# MCU.net
KiCad netlist of a schematic drawn in Altium Designer
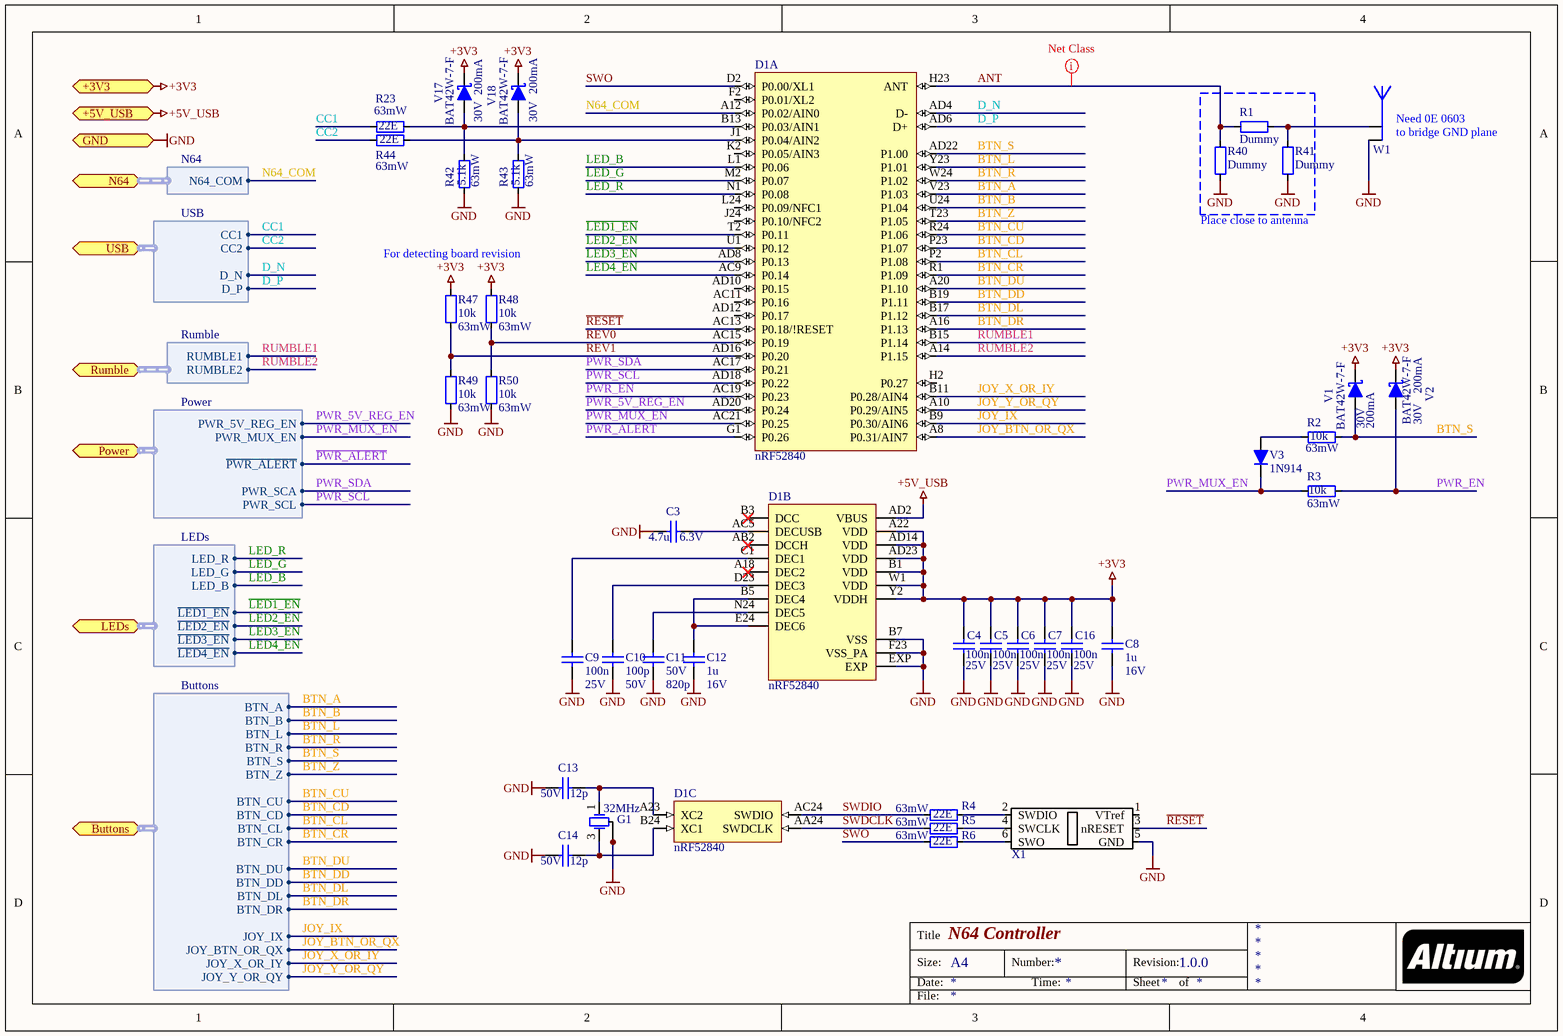
[diagram p0: MCU.SchDoc]

(export (version "E")
  (design (tool "Eeschema 10.0.6"))
  (components
    (comp (ref "C3")
      (value "4.7u")
      (footprint "SMD_CAP_0603")
      (fields (field (name "VALUE2") "6.3V") (field (name "Comment") "C_SMD_CER_4U7_6V3_10%_X5R_0603"))
      (libsource (lib "AM") (part "C_SMD_CER_4U7_6V3_10%_X5R_0603"))
    )
    (comp (ref "C4")
      (value "100n")
      (footprint "SMD_CAP_0402")
      (description "0.1µF ±10% 25V Ceramic Capacitor X7R 0402 (1005 Metric)")
      (fields (field (name "VALUE2") "25V") (field (name "Comment") "C_SMD_CER_100N_25V_10%_X7R_0402"))
      (libsource (lib "AM") (part "C_SMD_CER_100N_25V_10%_X7R_0402"))
    )
    (comp (ref "C5")
      (value "100n")
      (footprint "SMD_CAP_0402")
      (description "0.1µF ±10% 25V Ceramic Capacitor X7R 0402 (1005 Metric)")
      (fields (field (name "VALUE2") "25V") (field (name "Comment") "C_SMD_CER_100N_25V_10%_X7R_0402"))
      (libsource (lib "AM") (part "C_SMD_CER_100N_25V_10%_X7R_0402"))
    )
    (comp (ref "C6")
      (value "100n")
      (footprint "SMD_CAP_0402")
      (description "0.1µF ±10% 25V Ceramic Capacitor X7R 0402 (1005 Metric)")
      (fields (field (name "VALUE2") "25V") (field (name "Comment") "C_SMD_CER_100N_25V_10%_X7R_0402"))
      (libsource (lib "AM") (part "C_SMD_CER_100N_25V_10%_X7R_0402"))
    )
    (comp (ref "C7")
      (value "100n")
      (footprint "SMD_CAP_0402")
      (description "0.1µF ±10% 25V Ceramic Capacitor X7R 0402 (1005 Metric)")
      (fields (field (name "VALUE2") "25V") (field (name "Comment") "C_SMD_CER_100N_25V_10%_X7R_0402"))
      (libsource (lib "AM") (part "C_SMD_CER_100N_25V_10%_X7R_0402"))
    )
    (comp (ref "C8")
      (value "1u")
      (footprint "SMD_CAP_0603")
      (description "1µF ±10% 16V Ceramic Capacitor X7R 0603 (1608 Metric)")
      (fields (field (name "VALUE2") "16V") (field (name "Comment") "C_SMD_CER_1U_16V_10%_X7R_0603"))
      (libsource (lib "AM") (part "C_SMD_CER_1U_16V_10%_X7R_0603"))
    )
    (comp (ref "C9")
      (value "100n")
      (footprint "SMD_CAP_0402")
      (description "0.1µF ±10% 25V Ceramic Capacitor X7R 0402 (1005 Metric)")
      (fields (field (name "VALUE2") "25V") (field (name "Comment") "C_SMD_CER_100N_25V_10%_X7R_0402"))
      (libsource (lib "AM") (part "C_SMD_CER_100N_25V_10%_X7R_0402"))
    )
    (comp (ref "C10")
      (value "100p")
      (footprint "SMD_CAP_0402")
      (fields (field (name "VALUE2") "50V") (field (name "Comment") "C_SMD_CER_100P_50V_5%_NP0_0402"))
      (libsource (lib "AM") (part "C_SMD_CER_100P_50V_5%_NP0_0402"))
    )
    (comp (ref "C11")
      (value "820p")
      (footprint "SMD_CAP_0402")
      (description "820pF ±5% 50V Ceramic Capacitor C0G, NP0 0402 (1005 Metric)")
      (fields (field (name "VALUE2") "50V") (field (name "Comment") "C_SMD_CER_820P_50V_5%_NP0_0402"))
      (libsource (lib "AM") (part "C_SMD_CER_820P_50V_5%_NP0_0402"))
    )
    (comp (ref "C12")
      (value "1u")
      (footprint "SMD_CAP_0603")
      (description "1µF ±10% 16V Ceramic Capacitor X7R 0603 (1608 Metric)")
      (fields (field (name "VALUE2") "16V") (field (name "Comment") "C_SMD_CER_1U_16V_10%_X7R_0603"))
      (libsource (lib "AM") (part "C_SMD_CER_1U_16V_10%_X7R_0603"))
    )
    (comp (ref "C13")
      (value "12p")
      (footprint "SMD_CAP_0402")
      (description "12pF ±2% 50V Ceramic Capacitor C0G, NP0 0402 (1005 Metric)")
      (fields (field (name "VALUE2") "50V") (field (name "Comment") "C_SMD_CER_12P_50V_2%_NP0_0402"))
      (libsource (lib "AM") (part "C_SMD_CER_12P_50V_2%_NP0_0402"))
    )
    (comp (ref "C14")
      (value "12p")
      (footprint "SMD_CAP_0402")
      (description "12pF ±2% 50V Ceramic Capacitor C0G, NP0 0402 (1005 Metric)")
      (fields (field (name "VALUE2") "50V") (field (name "Comment") "C_SMD_CER_12P_50V_2%_NP0_0402"))
      (libsource (lib "AM") (part "C_SMD_CER_12P_50V_2%_NP0_0402"))
    )
    (comp (ref "C16")
      (value "100n")
      (footprint "SMD_CAP_0402")
      (description "0.1µF ±10% 25V Ceramic Capacitor X7R 0402 (1005 Metric)")
      (fields (field (name "VALUE2") "25V") (field (name "Comment") "C_SMD_CER_100N_25V_10%_X7R_0402"))
      (libsource (lib "AM") (part "C_SMD_CER_100N_25V_10%_X7R_0402"))
    )
    (comp (ref "D1")
      (value "D_NRF52840_aQFN-73")
      (footprint "SMD_aQFN_73_nRF52840")
      (description "IC RF TxRx + MCU 802.15.4, Bluetooth Bluetooth v5.0 2.4GHz 73-VFQFN Dual Rows, Exposed Pad")
      (fields (field (name "TYPE") "nRF52840"))
      (libsource (lib "") (part "D_NRF52840_aQFN-73_1"))
    )
    (comp (ref "G1")
      (value "32MHz")
      (footprint "SMD_QUARZ_3.2X2.5")
      (description "32MHz ±10ppm Crystal 8pF 40 Ohms 4-SMD, No Lead")
      (fields (field (name "Comment") "G_SMD_OSC_XTAL_32MHZ_10PPM_8PF_40OHM"))
      (libsource (lib "AM") (part "G_SMD_OSC_XTAL_32MHZ_10PPM_8PF_40OHM"))
    )
    (comp (ref "R1")
      (value "Dummy")
      (footprint "SMD_RES_0402")
      (description "Dummy 0402")
      (libsource (lib "AM") (part "R_SMD_DUMMY_0402"))
    )
    (comp (ref "R2")
      (value "10k")
      (footprint "SMD_RES_0402")
      (description "SMD Resistor")
      (fields
        (field (name "VALUE2") "63mW")
        (field (name "Comment") "R_SMD_THINFILM_10K_0W063_0%5_25PPM_0402")
      )
      (libsource (lib "AM") (part "R_SMD_THINFILM_10K_0W063_0%5_25PPM_0402"))
    )
    (comp (ref "R3")
      (value "10k")
      (footprint "SMD_RES_0402")
      (description "SMD Resistor")
      (fields
        (field (name "VALUE2") "63mW")
        (field (name "Comment") "R_SMD_THINFILM_10K_0W063_0%5_25PPM_0402")
      )
      (libsource (lib "AM") (part "R_SMD_THINFILM_10K_0W063_0%5_25PPM_0402"))
    )
    (comp (ref "R4")
      (value "22E")
      (footprint "SMD_RES_0402")
      (description "22 Ohms ±1% 0.063W, 1/16W Chip Resistor 0402 (1005 Metric) Moisture Resistant Thick Film")
      (fields
        (field (name "VALUE2") "63mW")
        (field (name "Comment") "R_SMD_THICKFILM_22E_0W063_1%_100PPM_0402")
      )
      (libsource (lib "AM") (part "R_SMD_THICKFILM_22E_0W063_1%_100PPM_0402"))
    )
    (comp (ref "R5")
      (value "22E")
      (footprint "SMD_RES_0402")
      (description "22 Ohms ±1% 0.063W, 1/16W Chip Resistor 0402 (1005 Metric) Moisture Resistant Thick Film")
      (fields
        (field (name "VALUE2") "63mW")
        (field (name "Comment") "R_SMD_THICKFILM_22E_0W063_1%_100PPM_0402")
      )
      (libsource (lib "AM") (part "R_SMD_THICKFILM_22E_0W063_1%_100PPM_0402"))
    )
    (comp (ref "R6")
      (value "22E")
      (footprint "SMD_RES_0402")
      (description "22 Ohms ±1% 0.063W, 1/16W Chip Resistor 0402 (1005 Metric) Moisture Resistant Thick Film")
      (fields
        (field (name "VALUE2") "63mW")
        (field (name "Comment") "R_SMD_THICKFILM_22E_0W063_1%_100PPM_0402")
      )
      (libsource (lib "AM") (part "R_SMD_THICKFILM_22E_0W063_1%_100PPM_0402"))
    )
    (comp (ref "R23")
      (value "22E")
      (footprint "SMD_RES_0402")
      (description "22 Ohms ±1% 0.063W, 1/16W Chip Resistor 0402 (1005 Metric) Moisture Resistant Thick Film")
      (fields
        (field (name "VALUE2") "63mW")
        (field (name "Comment") "R_SMD_THICKFILM_22E_0W063_1%_100PPM_0402")
      )
      (libsource (lib "AM") (part "R_SMD_THICKFILM_22E_0W063_1%_100PPM_0402"))
    )
    (comp (ref "R40")
      (value "Dummy")
      (footprint "SMD_RES_0402")
      (description "Dummy 0402")
      (libsource (lib "AM") (part "R_SMD_DUMMY_0402"))
    )
    (comp (ref "R41")
      (value "Dummy")
      (footprint "SMD_RES_0402")
      (description "Dummy 0402")
      (libsource (lib "AM") (part "R_SMD_DUMMY_0402"))
    )
    (comp (ref "R42")
      (value "5.1k")
      (footprint "SMD_CAP_0402")
      (description "5.1 kOhms ±0.5% 0.063W, 1/16W Chip Resistor 0402 (1005 Metric) Automotive AEC-Q200 Thin Film")
      (fields
        (field (name "VALUE2") "63mW")
        (field (name "Comment") "R_SMD_THINFILM_5K1_0W063_0%5_25PPM_0402")
      )
      (libsource (lib "AM") (part "R_SMD_THINFILM_5K1_0W063_0%5_25PPM_0402"))
    )
    (comp (ref "R43")
      (value "5.1k")
      (footprint "SMD_CAP_0402")
      (description "5.1 kOhms ±0.5% 0.063W, 1/16W Chip Resistor 0402 (1005 Metric) Automotive AEC-Q200 Thin Film")
      (fields
        (field (name "VALUE2") "63mW")
        (field (name "Comment") "R_SMD_THINFILM_5K1_0W063_0%5_25PPM_0402")
      )
      (libsource (lib "AM") (part "R_SMD_THINFILM_5K1_0W063_0%5_25PPM_0402"))
    )
    (comp (ref "R44")
      (value "22E")
      (footprint "SMD_RES_0402")
      (description "22 Ohms ±1% 0.063W, 1/16W Chip Resistor 0402 (1005 Metric) Moisture Resistant Thick Film")
      (fields
        (field (name "VALUE2") "63mW")
        (field (name "Comment") "R_SMD_THICKFILM_22E_0W063_1%_100PPM_0402")
      )
      (libsource (lib "AM") (part "R_SMD_THICKFILM_22E_0W063_1%_100PPM_0402"))
    )
    (comp (ref "R47")
      (value "10k")
      (footprint "SMD_RES_0402")
      (description "SMD Resistor")
      (fields
        (field (name "VALUE2") "63mW")
        (field (name "Comment") "R_SMD_THINFILM_10K_0W063_0%5_25PPM_0402")
      )
      (libsource (lib "AM") (part "R_SMD_THINFILM_10K_0W063_0%5_25PPM_0402"))
    )
    (comp (ref "R48")
      (value "10k")
      (footprint "SMD_RES_0402")
      (description "SMD Resistor")
      (fields
        (field (name "VALUE2") "63mW")
        (field (name "Comment") "R_SMD_THINFILM_10K_0W063_0%5_25PPM_0402")
      )
      (libsource (lib "AM") (part "R_SMD_THINFILM_10K_0W063_0%5_25PPM_0402"))
    )
    (comp (ref "R49")
      (value "10k")
      (footprint "SMD_RES_0402")
      (description "SMD Resistor")
      (fields
        (field (name "VALUE2") "63mW")
        (field (name "Comment") "R_SMD_THINFILM_10K_0W063_0%5_25PPM_0402")
      )
      (libsource (lib "AM") (part "R_SMD_THINFILM_10K_0W063_0%5_25PPM_0402"))
    )
    (comp (ref "R50")
      (value "10k")
      (footprint "SMD_RES_0402")
      (description "SMD Resistor")
      (fields
        (field (name "VALUE2") "63mW")
        (field (name "Comment") "R_SMD_THINFILM_10K_0W063_0%5_25PPM_0402")
      )
      (libsource (lib "AM") (part "R_SMD_THINFILM_10K_0W063_0%5_25PPM_0402"))
    )
    (comp (ref "V1")
      (value "30V")
      (footprint "SMD_SOD_123")
      (description "Diode Schottky 30V 200mA (DC) Surface Mount SOD-123")
      (fields
        (field (name "TYPE") "BAT42W-7-F")
        (field (name "VALUE2") "200mA")
        (field (name "Comment") "V_SMD_SCHOTTKY_BAT42W-7-F_30V_0A2_SOD-123")
      )
      (libsource (lib "AM") (part "V_SMD_SCHOTTKY_BAT42W-7-F_30V_0A2_SOD-123"))
    )
    (comp (ref "V2")
      (value "30V")
      (footprint "SMD_SOD_123")
      (description "Diode Schottky 30V 200mA (DC) Surface Mount SOD-123")
      (fields
        (field (name "TYPE") "BAT42W-7-F")
        (field (name "VALUE2") "200mA")
        (field (name "Comment") "V_SMD_SCHOTTKY_BAT42W-7-F_30V_0A2_SOD-123")
      )
      (libsource (lib "AM") (part "V_SMD_SCHOTTKY_BAT42W-7-F_30V_0A2_SOD-123"))
    )
    (comp (ref "V3")
      (value "V_SMD_DIODE_1N914_75V_0A15_SOD-323")
      (footprint "SMD_SOD_323")
      (description "SMD Diode, 75V, 0.15A")
      (fields (field (name "TYPE") "1N914"))
      (libsource (lib "AM") (part "V_SMD_DIODE_1N914_75V_0A15_SOD-323"))
    )
    (comp (ref "V17")
      (value "30V")
      (footprint "SMD_SOD_123")
      (description "Diode Schottky 30V 200mA (DC) Surface Mount SOD-123")
      (fields
        (field (name "TYPE") "BAT42W-7-F")
        (field (name "VALUE2") "200mA")
        (field (name "Comment") "V_SMD_SCHOTTKY_BAT42W-7-F_30V_0A2_SOD-123")
      )
      (libsource (lib "AM") (part "V_SMD_SCHOTTKY_BAT42W-7-F_30V_0A2_SOD-123"))
    )
    (comp (ref "V18")
      (value "30V")
      (footprint "SMD_SOD_123")
      (description "Diode Schottky 30V 200mA (DC) Surface Mount SOD-123")
      (fields
        (field (name "TYPE") "BAT42W-7-F")
        (field (name "VALUE2") "200mA")
        (field (name "Comment") "V_SMD_SCHOTTKY_BAT42W-7-F_30V_0A2_SOD-123")
      )
      (libsource (lib "AM") (part "V_SMD_SCHOTTKY_BAT42W-7-F_30V_0A2_SOD-123"))
    )
    (comp (ref "W1")
      (value "W_BLUETOOTH_IFA_1MM")
      (footprint "BLUETOOTH_IFA_1MM")
      (description "Single Layer Printed IFA, 1 mm Substrate")
      (libsource (lib "AM") (part "W_BLUETOOTH_IFA_1MM"))
    )
    (comp (ref "X1")
      (value "X_J-LINK_6-PIN_NEEDLE_HEADER")
      (footprint "SMD_J-LINK_6-PIN_NEEDLE")
      (description "J-Link 6-pin Needle Adapter (8.06.16)")
      (libsource (lib "AM") (part "X_J-LINK_6-PIN_NEEDLE_HEADER"))
    )
  )
  (nets
    (net (code "7") (name "+3V3") (class "Default")
      (node (ref "C16") (pin "2") (pinfunction "2_2") (pintype "passive"))
      (node (ref "C4") (pin "2") (pinfunction "2_2") (pintype "passive"))
      (node (ref "C5") (pin "2") (pinfunction "2_2") (pintype "passive"))
      (node (ref "C6") (pin "2") (pinfunction "2_2") (pintype "passive"))
      (node (ref "C7") (pin "2") (pinfunction "2_2") (pintype "passive"))
      (node (ref "C8") (pin "2") (pinfunction "2_2") (pintype "passive"))
      (node (ref "D1") (pin "A22") (pinfunction "VDD_A22") (pintype "power_in"))
      (node (ref "D1") (pin "AD14") (pinfunction "VDD_AD14") (pintype "power_in"))
      (node (ref "D1") (pin "AD23") (pinfunction "VDD_AD23") (pintype "power_in"))
      (node (ref "D1") (pin "B1") (pinfunction "VDD_B1") (pintype "power_in"))
      (node (ref "D1") (pin "W1") (pinfunction "VDD_W1") (pintype "power_in"))
      (node (ref "D1") (pin "Y2") (pinfunction "VDDH_Y2") (pintype "power_in"))
      (node (ref "R47") (pin "1") (pinfunction "1_1") (pintype "passive"))
      (node (ref "R48") (pin "1") (pinfunction "1_1") (pintype "passive"))
      (node (ref "V1") (pin "2") (pinfunction "2_2") (pintype "passive"))
      (node (ref "V17") (pin "2") (pinfunction "2_2") (pintype "passive"))
      (node (ref "V18") (pin "2") (pinfunction "2_2") (pintype "passive"))
      (node (ref "V2") (pin "2") (pinfunction "2_2") (pintype "passive"))
    )
    (net (code "8") (name "+5V_USB") (class "Default")
      (node (ref "D1") (pin "AD2") (pinfunction "VBUS_AD2") (pintype "power_in"))
    )
    (net (code "9") (name "/ANT") (class "Default")
      (node (ref "D1") (pin "H23") (pinfunction "ANT_H23") (pintype "bidirectional"))
      (node (ref "R1") (pin "1") (pinfunction "1_1") (pintype "passive"))
      (node (ref "R40") (pin "2") (pinfunction "2_2") (pintype "passive"))
    )
    (net (code "10") (name "/BTN_A") (class "Default")
      (node (ref "D1") (pin "V23") (pinfunction "P1.03_V23") (pintype "bidirectional"))
    )
    (net (code "11") (name "/BTN_B") (class "Default")
      (node (ref "D1") (pin "U24") (pinfunction "P1.04_U24") (pintype "bidirectional"))
    )
    (net (code "12") (name "/BTN_CD") (class "Default")
      (node (ref "D1") (pin "P23") (pinfunction "P1.07_P23") (pintype "bidirectional"))
    )
    (net (code "13") (name "/BTN_CL") (class "Default")
      (node (ref "D1") (pin "P2") (pinfunction "P1.08_P2") (pintype "bidirectional"))
    )
    (net (code "14") (name "/BTN_CR") (class "Default")
      (node (ref "D1") (pin "R1") (pinfunction "P1.09_R1") (pintype "bidirectional"))
    )
    (net (code "15") (name "/BTN_CU") (class "Default")
      (node (ref "D1") (pin "R24") (pinfunction "P1.06_R24") (pintype "bidirectional"))
    )
    (net (code "16") (name "/BTN_DD") (class "Default")
      (node (ref "D1") (pin "B19") (pinfunction "P1.11_B19") (pintype "bidirectional"))
    )
    (net (code "17") (name "/BTN_DL") (class "Default")
      (node (ref "D1") (pin "B17") (pinfunction "P1.12_B17") (pintype "bidirectional"))
    )
    (net (code "18") (name "/BTN_DR") (class "Default")
      (node (ref "D1") (pin "A16") (pinfunction "P1.13_A16") (pintype "bidirectional"))
    )
    (net (code "19") (name "/BTN_DU") (class "Default")
      (node (ref "D1") (pin "A20") (pinfunction "P1.10_A20") (pintype "bidirectional"))
    )
    (net (code "20") (name "/BTN_L") (class "Default")
      (node (ref "D1") (pin "Y23") (pinfunction "P1.01_Y23") (pintype "bidirectional"))
    )
    (net (code "21") (name "/BTN_R") (class "Default")
      (node (ref "D1") (pin "W24") (pinfunction "P1.02_W24") (pintype "bidirectional"))
    )
    (net (code "22") (name "/BTN_S") (class "Default")
      (node (ref "D1") (pin "AD22") (pinfunction "P1.00_AD22") (pintype "bidirectional"))
      (node (ref "R2") (pin "2") (pinfunction "2_2") (pintype "passive"))
      (node (ref "V1") (pin "1") (pinfunction "1_1") (pintype "passive"))
    )
    (net (code "23") (name "/BTN_Z") (class "Default")
      (node (ref "D1") (pin "T23") (pinfunction "P1.05_T23") (pintype "bidirectional"))
    )
    (net (code "24") (name "/CC1") (class "Default")
      (node (ref "R23") (pin "1") (pinfunction "1_1") (pintype "passive"))
    )
    (net (code "25") (name "/CC2") (class "Default")
      (node (ref "R44") (pin "1") (pinfunction "1_1") (pintype "passive"))
    )
    (net (code "26") (name "/D_N") (class "Default")
      (node (ref "D1") (pin "AD4") (pinfunction "D-_AD4") (pintype "bidirectional"))
    )
    (net (code "27") (name "/D_P") (class "Default")
      (node (ref "D1") (pin "AD6") (pinfunction "D+_AD6") (pintype "bidirectional"))
    )
    (net (code "28") (name "/JOY_BTN_OR_QX") (class "Default")
      (node (ref "D1") (pin "A8") (pinfunction "P0.31/AIN7_A8") (pintype "bidirectional"))
    )
    (net (code "29") (name "/JOY_IX") (class "Default")
      (node (ref "D1") (pin "B9") (pinfunction "P0.30/AIN6_B9") (pintype "bidirectional"))
    )
    (net (code "30") (name "/JOY_X_OR_IY") (class "Default")
      (node (ref "D1") (pin "B11") (pinfunction "P0.28/AIN4_B11") (pintype "bidirectional"))
    )
    (net (code "31") (name "/JOY_Y_OR_QY") (class "Default")
      (node (ref "D1") (pin "A10") (pinfunction "P0.29/AIN5_A10") (pintype "bidirectional"))
    )
    (net (code "32") (name "/LED_B") (class "Default")
      (node (ref "D1") (pin "L1") (pinfunction "P0.06_L1") (pintype "bidirectional"))
    )
    (net (code "33") (name "/LED_G") (class "Default")
      (node (ref "D1") (pin "M2") (pinfunction "P0.07_M2") (pintype "bidirectional"))
    )
    (net (code "34") (name "/LED_R") (class "Default")
      (node (ref "D1") (pin "N1") (pinfunction "P0.08_N1") (pintype "bidirectional"))
    )
    (net (code "35") (name "/N64_COM") (class "Default")
      (node (ref "D1") (pin "A12") (pinfunction "P0.02/AIN0_A12") (pintype "bidirectional"))
    )
    (net (code "36") (name "/PWR_5V_REG_EN") (class "Default")
      (node (ref "D1") (pin "AD20") (pinfunction "P0.24_AD20") (pintype "bidirectional"))
    )
    (net (code "37") (name "/PWR_EN") (class "Default")
      (node (ref "D1") (pin "AC19") (pinfunction "P0.23_AC19") (pintype "bidirectional"))
      (node (ref "R3") (pin "2") (pinfunction "2_2") (pintype "passive"))
      (node (ref "V2") (pin "1") (pinfunction "1_1") (pintype "passive"))
    )
    (net (code "38") (name "/PWR_MUX_EN") (class "Default")
      (node (ref "D1") (pin "AC21") (pinfunction "P0.25_AC21") (pintype "bidirectional"))
      (node (ref "R3") (pin "1") (pinfunction "1_1") (pintype "passive"))
      (node (ref "V3") (pin "2") (pinfunction "2_2") (pintype "passive"))
    )
    (net (code "39") (name "/PWR_SCL") (class "Default")
      (node (ref "D1") (pin "AD18") (pinfunction "P0.22_AD18") (pintype "bidirectional"))
    )
    (net (code "40") (name "/PWR_SDA") (class "Default")
      (node (ref "D1") (pin "AC17") (pinfunction "P0.21_AC17") (pintype "bidirectional"))
    )
    (net (code "41") (name "/REV0") (class "Default")
      (node (ref "D1") (pin "AC15") (pinfunction "P0.19_AC15") (pintype "bidirectional"))
      (node (ref "R48") (pin "2") (pinfunction "2_2") (pintype "passive"))
      (node (ref "R50") (pin "1") (pinfunction "1_1") (pintype "passive"))
    )
    (net (code "42") (name "/REV1") (class "Default")
      (node (ref "D1") (pin "AD16") (pinfunction "P0.20_AD16") (pintype "bidirectional"))
      (node (ref "R47") (pin "2") (pinfunction "2_2") (pintype "passive"))
      (node (ref "R49") (pin "1") (pinfunction "1_1") (pintype "passive"))
    )
    (net (code "43") (name "/RUMBLE1") (class "Default")
      (node (ref "D1") (pin "B15") (pinfunction "P1.14_B15") (pintype "bidirectional"))
    )
    (net (code "44") (name "/RUMBLE2") (class "Default")
      (node (ref "D1") (pin "A14") (pinfunction "P1.15_A14") (pintype "bidirectional"))
    )
    (net (code "45") (name "/SWDCLK") (class "Default")
      (node (ref "D1") (pin "AA24") (pinfunction "SWDCLK_AA24") (pintype "input"))
      (node (ref "R5") (pin "1") (pinfunction "1_1") (pintype "passive"))
    )
    (net (code "46") (name "/SWDIO") (class "Default")
      (node (ref "D1") (pin "AC24") (pinfunction "SWDIO_AC24") (pintype "input"))
      (node (ref "R4") (pin "1") (pinfunction "1_1") (pintype "passive"))
    )
    (net (code "47") (name "/SWO") (class "Default")
      (node (ref "D1") (pin "D2") (pinfunction "P0.00/XL1_D2") (pintype "bidirectional"))
      (node (ref "R6") (pin "1") (pinfunction "1_1") (pintype "passive"))
    )
    (net (code "54") (name "/~{LED1_EN}") (class "Default")
      (node (ref "D1") (pin "T2") (pinfunction "P0.11_T2") (pintype "bidirectional"))
    )
    (net (code "55") (name "/~{LED2_EN}") (class "Default")
      (node (ref "D1") (pin "U1") (pinfunction "P0.12_U1") (pintype "bidirectional"))
    )
    (net (code "56") (name "/~{LED3_EN}") (class "Default")
      (node (ref "D1") (pin "AD8") (pinfunction "P0.13_AD8") (pintype "bidirectional"))
    )
    (net (code "57") (name "/~{LED4_EN}") (class "Default")
      (node (ref "D1") (pin "AC9") (pinfunction "P0.14_AC9") (pintype "bidirectional"))
    )
    (net (code "58") (name "/~{PWR_ALERT}") (class "Default")
      (node (ref "D1") (pin "G1") (pinfunction "P0.26_G1") (pintype "bidirectional"))
    )
    (net (code "59") (name "/~{RESET}") (class "Default")
      (node (ref "D1") (pin "AC13") (pinfunction "P0.18/!RESET_AC13") (pintype "bidirectional"))
      (node (ref "X1") (pin "3") (pinfunction "nRESET_3") (pintype "passive"))
    )
    (net (code "60") (name "GND") (class "Default")
      (node (ref "C10") (pin "1") (pinfunction "1_1") (pintype "passive"))
      (node (ref "C11") (pin "1") (pinfunction "1_1") (pintype "passive"))
      (node (ref "C12") (pin "1") (pinfunction "1_1") (pintype "passive"))
      (node (ref "C13") (pin "1") (pinfunction "1_1") (pintype "passive"))
      (node (ref "C14") (pin "1") (pinfunction "1_1") (pintype "passive"))
      (node (ref "C16") (pin "1") (pinfunction "1_1") (pintype "passive"))
      (node (ref "C3") (pin "1") (pinfunction "1_1") (pintype "passive"))
      (node (ref "C4") (pin "1") (pinfunction "1_1") (pintype "passive"))
      (node (ref "C5") (pin "1") (pinfunction "1_1") (pintype "passive"))
      (node (ref "C6") (pin "1") (pinfunction "1_1") (pintype "passive"))
      (node (ref "C7") (pin "1") (pinfunction "1_1") (pintype "passive"))
      (node (ref "C8") (pin "1") (pinfunction "1_1") (pintype "passive"))
      (node (ref "C9") (pin "2") (pinfunction "2_2") (pintype "passive"))
      (node (ref "D1") (pin "B7") (pinfunction "VSS_B7") (pintype "power_in"))
      (node (ref "D1") (pin "EXP") (pinfunction "EXP_EXP") (pintype "power_in"))
      (node (ref "D1") (pin "F23") (pinfunction "VSS_PA_F23") (pintype "power_in"))
      (node (ref "G1") (pin "2") (pinfunction "2_2") (pintype "passive"))
      (node (ref "G1") (pin "4") (pinfunction "4_4") (pintype "passive"))
      (node (ref "R40") (pin "1") (pinfunction "1_1") (pintype "passive"))
      (node (ref "R41") (pin "1") (pinfunction "1_1") (pintype "passive"))
      (node (ref "R42") (pin "1") (pinfunction "1_1") (pintype "passive"))
      (node (ref "R43") (pin "1") (pinfunction "1_1") (pintype "passive"))
      (node (ref "R49") (pin "2") (pinfunction "2_2") (pintype "passive"))
      (node (ref "R50") (pin "2") (pinfunction "2_2") (pintype "passive"))
      (node (ref "W1") (pin "1") (pinfunction "GND_1") (pintype "passive"))
      (node (ref "X1") (pin "5") (pinfunction "GND_5") (pintype "passive"))
    )
    (net (code "61") (name "Net-(D1A-P0.03{slash}AIN1)") (class "Default")
      (node (ref "D1") (pin "B13") (pinfunction "P0.03/AIN1_B13") (pintype "bidirectional"))
      (node (ref "R23") (pin "2") (pinfunction "2_2") (pintype "passive"))
      (node (ref "R42") (pin "2") (pinfunction "2_2") (pintype "passive"))
      (node (ref "V17") (pin "1") (pinfunction "1_1") (pintype "passive"))
    )
    (net (code "62") (name "Net-(D1A-P0.04{slash}AIN2)") (class "Default")
      (node (ref "D1") (pin "J1") (pinfunction "P0.04/AIN2_J1") (pintype "bidirectional"))
      (node (ref "R43") (pin "2") (pinfunction "2_2") (pintype "passive"))
      (node (ref "R44") (pin "2") (pinfunction "2_2") (pintype "passive"))
      (node (ref "V18") (pin "1") (pinfunction "1_1") (pintype "passive"))
    )
    (net (code "63") (name "Net-(D1B-DEC1)") (class "Default")
      (node (ref "C9") (pin "1") (pinfunction "1_1") (pintype "passive"))
      (node (ref "D1") (pin "C1") (pinfunction "DEC1_C1") (pintype "power_in"))
    )
    (net (code "64") (name "Net-(D1B-DEC3)") (class "Default")
      (node (ref "C10") (pin "2") (pinfunction "2_2") (pintype "passive"))
      (node (ref "D1") (pin "D23") (pinfunction "DEC3_D23") (pintype "power_in"))
    )
    (net (code "65") (name "Net-(D1B-DEC4)") (class "Default")
      (node (ref "C12") (pin "2") (pinfunction "2_2") (pintype "passive"))
      (node (ref "D1") (pin "B5") (pinfunction "DEC4_B5") (pintype "power_in"))
      (node (ref "D1") (pin "E24") (pinfunction "DEC6_E24") (pintype "power_in"))
    )
    (net (code "66") (name "Net-(D1B-DEC5)") (class "Default")
      (node (ref "C11") (pin "2") (pinfunction "2_2") (pintype "passive"))
      (node (ref "D1") (pin "N24") (pinfunction "DEC5_N24") (pintype "power_in"))
    )
    (net (code "67") (name "Net-(D1B-DECUSB)") (class "Default")
      (node (ref "C3") (pin "2") (pinfunction "2_2") (pintype "passive"))
      (node (ref "D1") (pin "AC5") (pinfunction "DECUSB_AC5") (pintype "power_in"))
    )
    (net (code "68") (name "Net-(D1C-XC1)") (class "Default")
      (node (ref "C14") (pin "2") (pinfunction "2_2") (pintype "passive"))
      (node (ref "D1") (pin "B24") (pinfunction "XC1_B24") (pintype "input"))
      (node (ref "G1") (pin "3") (pinfunction "OSC2_3") (pintype "passive"))
    )
    (net (code "69") (name "Net-(D1C-XC2)") (class "Default")
      (node (ref "C13") (pin "2") (pinfunction "2_2") (pintype "passive"))
      (node (ref "D1") (pin "A23") (pinfunction "XC2_A23") (pintype "input"))
      (node (ref "G1") (pin "1") (pinfunction "OSC1_1") (pintype "passive"))
    )
    (net (code "70") (name "Net-(R2-Pad1)") (class "Default")
      (node (ref "R2") (pin "1") (pinfunction "1_1") (pintype "passive"))
      (node (ref "V3") (pin "1") (pinfunction "1_1") (pintype "passive"))
    )
    (net (code "71") (name "Net-(W1-Feed)") (class "Default")
      (node (ref "R1") (pin "2") (pinfunction "2_2") (pintype "passive"))
      (node (ref "R41") (pin "2") (pinfunction "2_2") (pintype "passive"))
      (node (ref "W1") (pin "2") (pinfunction "Feed_2") (pintype "passive"))
    )
    (net (code "72") (name "Net-(X1-SWCLK)") (class "Default")
      (node (ref "R5") (pin "2") (pinfunction "2_2") (pintype "passive"))
      (node (ref "X1") (pin "4") (pinfunction "SWCLK_4") (pintype "passive"))
    )
    (net (code "73") (name "Net-(X1-SWDIO)") (class "Default")
      (node (ref "R4") (pin "2") (pinfunction "2_2") (pintype "passive"))
      (node (ref "X1") (pin "2") (pinfunction "SWDIO_2") (pintype "passive"))
    )
    (net (code "74") (name "Net-(X1-SWO)") (class "Default")
      (node (ref "R6") (pin "2") (pinfunction "2_2") (pintype "passive"))
      (node (ref "X1") (pin "6") (pinfunction "SWO_6") (pintype "passive"))
    )
    (net (code "75") (name "unconnected-(D1A-P0.01{slash}XL2-PadF2)") (class "Default")
      (node (ref "D1") (pin "F2") (pinfunction "P0.01/XL2_F2") (pintype "bidirectional"))
    )
    (net (code "76") (name "unconnected-(D1A-P0.05{slash}AIN3-PadK2)") (class "Default")
      (node (ref "D1") (pin "K2") (pinfunction "P0.05/AIN3_K2") (pintype "bidirectional"))
    )
    (net (code "77") (name "unconnected-(D1A-P0.09{slash}NFC1-PadL24)") (class "Default")
      (node (ref "D1") (pin "L24") (pinfunction "P0.09/NFC1_L24") (pintype "bidirectional"))
    )
    (net (code "78") (name "unconnected-(D1A-P0.10{slash}NFC2-PadJ24)") (class "Default")
      (node (ref "D1") (pin "J24") (pinfunction "P0.10/NFC2_J24") (pintype "bidirectional"))
    )
    (net (code "79") (name "unconnected-(D1A-P0.15-PadAD10)") (class "Default")
      (node (ref "D1") (pin "AD10") (pinfunction "P0.15_AD10") (pintype "bidirectional"))
    )
    (net (code "80") (name "unconnected-(D1A-P0.16-PadAC11)") (class "Default")
      (node (ref "D1") (pin "AC11") (pinfunction "P0.16_AC11") (pintype "bidirectional"))
    )
    (net (code "81") (name "unconnected-(D1A-P0.17-PadAD12)") (class "Default")
      (node (ref "D1") (pin "AD12") (pinfunction "P0.17_AD12") (pintype "bidirectional"))
    )
    (net (code "82") (name "unconnected-(D1A-P0.27-PadH2)") (class "Default")
      (node (ref "D1") (pin "H2") (pinfunction "P0.27_H2") (pintype "bidirectional"))
    )
    (net (code "83") (name "unconnected-(D1B-DCC-PadB3)") (class "Default")
      (node (ref "D1") (pin "B3") (pinfunction "DCC_B3") (pintype "power_in+no_connect"))
    )
    (net (code "84") (name "unconnected-(D1B-DCCH-PadAB2)") (class "Default")
      (node (ref "D1") (pin "AB2") (pinfunction "DCCH_AB2") (pintype "power_in+no_connect"))
    )
    (net (code "85") (name "unconnected-(D1B-DEC2-PadA18)") (class "Default")
      (node (ref "D1") (pin "A18") (pinfunction "DEC2_A18") (pintype "power_in+no_connect"))
    )
    (net (code "86") (name "unconnected-(X1-VTref-Pad1)") (class "Default")
      (node (ref "X1") (pin "1") (pinfunction "VTref_1") (pintype "passive"))
    )
  )
)
